# uart-keyboard.net
KiCad netlist of a schematic drawn in Altium Designer
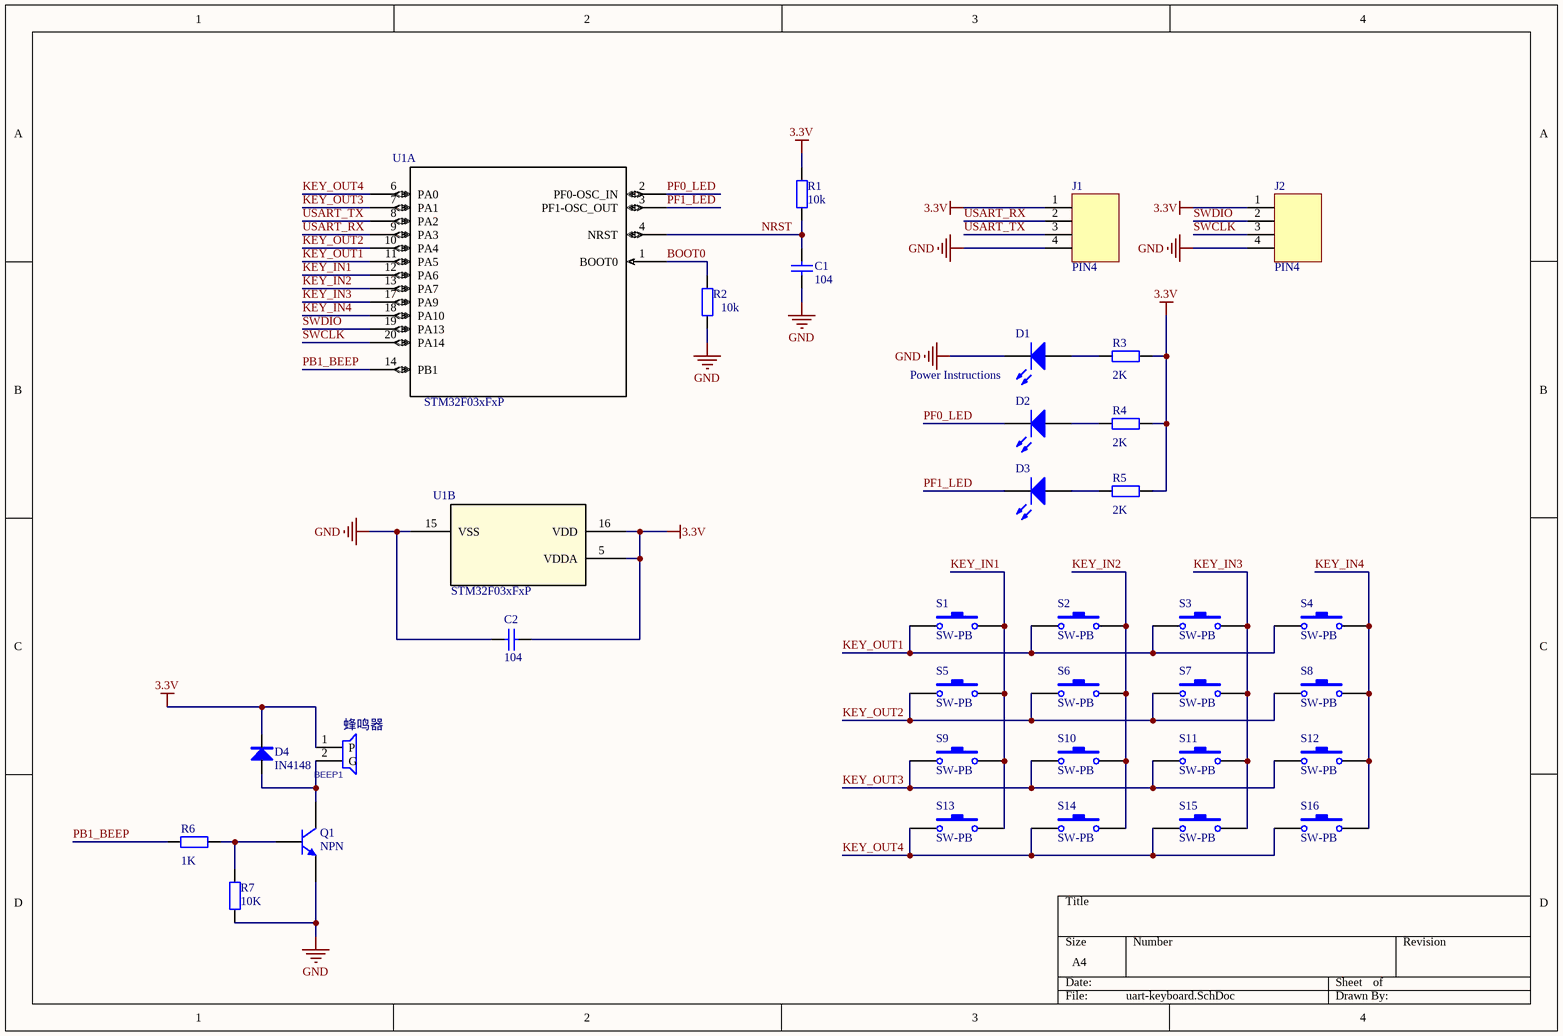
[diagram p0: uart-keyboard.SchDoc]

(export (version "E")
  (design (tool "Eeschema 10.0.6"))
  (components
    (comp (ref "BEEP1")
      (value "BEEP-9.5X5.5")
      (footprint "蜂鸣器")
      (libsource (lib "F429_F746_MB_SCH") (part "BEEP-9.5X5.5"))
    )
    (comp (ref "C1")
      (value "104")
      (footprint "0805C")
      (description "Capacitor")
      (fields (field (name "PUBLISHER") "Altium Limited"))
      (libsource (lib "Miscellaneous Devices") (part "Cap"))
    )
    (comp (ref "C2")
      (value "104")
      (footprint "0805C")
      (description "Capacitor")
      (fields (field (name "PUBLISHER") "Altium Limited"))
      (libsource (lib "Miscellaneous Devices") (part "Cap"))
    )
    (comp (ref "D1")
      (value "Power Instructions")
      (footprint "LED0805")
      (description "Typical RED, GREEN, YELLOW, AMBER GaAs LED")
      (fields (field (name "PUBLISHER") "Altium Limited"))
      (libsource (lib "Miscellaneous Devices") (part "LED2"))
    )
    (comp (ref "D2")
      (value "~")
      (footprint "LED0805")
      (description "Typical RED, GREEN, YELLOW, AMBER GaAs LED")
      (fields (field (name "PUBLISHER") "Altium Limited"))
      (libsource (lib "Miscellaneous Devices") (part "LED2"))
    )
    (comp (ref "D3")
      (value "~")
      (footprint "LED0805")
      (description "Typical RED, GREEN, YELLOW, AMBER GaAs LED")
      (fields (field (name "PUBLISHER") "Altium Limited"))
      (libsource (lib "Miscellaneous Devices") (part "LED2"))
    )
    (comp (ref "D4")
      (value "IN4148")
      (footprint "D4148")
      (libsource (lib "My Library OF Sch") (part "IN4148"))
    )
    (comp (ref "J1")
      (value "PIN4")
      (footprint "排针1*4-2.54-直")
      (libsource (lib "libpowersupply") (part "PIN4"))
    )
    (comp (ref "J2")
      (value "PIN4")
      (footprint "排针1*4-2.54-直")
      (libsource (lib "libpowersupply") (part "PIN4"))
    )
    (comp (ref "Q1")
      (value "NPN")
      (footprint "SOT-23-3")
      (description "NPN Bipolar Transistor")
      (fields (field (name "PUBLISHER") "Altium Limited"))
      (libsource (lib "Miscellaneous Devices") (part "NPN"))
    )
    (comp (ref "R1")
      (value "10k")
      (footprint "0805R")
      (description "Resistor")
      (fields (field (name "PUBLISHER") "Altium Limited"))
      (libsource (lib "") (part "Res2_1"))
    )
    (comp (ref "R2")
      (value "10k")
      (footprint "0805R")
      (description "Resistor")
      (fields (field (name "PUBLISHER") "Altium Limited"))
      (libsource (lib "") (part "Res2_2"))
    )
    (comp (ref "R3")
      (value "2K")
      (footprint "0805R")
      (description "Resistor")
      (fields (field (name "PUBLISHER") "Altium Limited"))
      (libsource (lib "Miscellaneous Devices") (part "Res2"))
    )
    (comp (ref "R4")
      (value "2K")
      (footprint "0805R")
      (description "Resistor")
      (fields (field (name "PUBLISHER") "Altium Limited"))
      (libsource (lib "Miscellaneous Devices") (part "Res2"))
    )
    (comp (ref "R5")
      (value "2K")
      (footprint "0805R")
      (description "Resistor")
      (fields (field (name "PUBLISHER") "Altium Limited"))
      (libsource (lib "Miscellaneous Devices") (part "Res2"))
    )
    (comp (ref "R6")
      (value "1K")
      (footprint "0805R")
      (description "Resistor")
      (fields (field (name "PUBLISHER") "Altium Limited"))
      (libsource (lib "Miscellaneous Devices") (part "Res2"))
    )
    (comp (ref "R7")
      (value "10K")
      (footprint "0805R")
      (description "Resistor")
      (fields (field (name "PUBLISHER") "Altium Limited"))
      (libsource (lib "") (part "Res2_3"))
    )
    (comp (ref "S1")
      (value "SW-PB")
      (footprint "轻触开关-6*6*5")
      (description "Switch")
      (fields (field (name "PUBLISHER") "Altium Limited"))
      (libsource (lib "Miscellaneous Devices") (part "SW-PB"))
    )
    (comp (ref "S2")
      (value "SW-PB")
      (footprint "轻触开关-6*6*5")
      (description "Switch")
      (fields (field (name "PUBLISHER") "Altium Limited"))
      (libsource (lib "Miscellaneous Devices") (part "SW-PB"))
    )
    (comp (ref "S3")
      (value "SW-PB")
      (footprint "轻触开关-6*6*5")
      (description "Switch")
      (fields (field (name "PUBLISHER") "Altium Limited"))
      (libsource (lib "Miscellaneous Devices") (part "SW-PB"))
    )
    (comp (ref "S4")
      (value "SW-PB")
      (footprint "轻触开关-6*6*5")
      (description "Switch")
      (fields (field (name "PUBLISHER") "Altium Limited"))
      (libsource (lib "Miscellaneous Devices") (part "SW-PB"))
    )
    (comp (ref "S5")
      (value "SW-PB")
      (footprint "轻触开关-6*6*5")
      (description "Switch")
      (fields (field (name "PUBLISHER") "Altium Limited"))
      (libsource (lib "Miscellaneous Devices") (part "SW-PB"))
    )
    (comp (ref "S6")
      (value "SW-PB")
      (footprint "轻触开关-6*6*5")
      (description "Switch")
      (fields (field (name "PUBLISHER") "Altium Limited"))
      (libsource (lib "Miscellaneous Devices") (part "SW-PB"))
    )
    (comp (ref "S7")
      (value "SW-PB")
      (footprint "轻触开关-6*6*5")
      (description "Switch")
      (fields (field (name "PUBLISHER") "Altium Limited"))
      (libsource (lib "Miscellaneous Devices") (part "SW-PB"))
    )
    (comp (ref "S8")
      (value "SW-PB")
      (footprint "轻触开关-6*6*5")
      (description "Switch")
      (fields (field (name "PUBLISHER") "Altium Limited"))
      (libsource (lib "Miscellaneous Devices") (part "SW-PB"))
    )
    (comp (ref "S9")
      (value "SW-PB")
      (footprint "轻触开关-6*6*5")
      (description "Switch")
      (fields (field (name "PUBLISHER") "Altium Limited"))
      (libsource (lib "Miscellaneous Devices") (part "SW-PB"))
    )
    (comp (ref "S10")
      (value "SW-PB")
      (footprint "轻触开关-6*6*5")
      (description "Switch")
      (fields (field (name "PUBLISHER") "Altium Limited"))
      (libsource (lib "Miscellaneous Devices") (part "SW-PB"))
    )
    (comp (ref "S11")
      (value "SW-PB")
      (footprint "轻触开关-6*6*5")
      (description "Switch")
      (fields (field (name "PUBLISHER") "Altium Limited"))
      (libsource (lib "Miscellaneous Devices") (part "SW-PB"))
    )
    (comp (ref "S12")
      (value "SW-PB")
      (footprint "轻触开关-6*6*5")
      (description "Switch")
      (fields (field (name "PUBLISHER") "Altium Limited"))
      (libsource (lib "Miscellaneous Devices") (part "SW-PB"))
    )
    (comp (ref "S13")
      (value "SW-PB")
      (footprint "轻触开关-6*6*5")
      (description "Switch")
      (fields (field (name "PUBLISHER") "Altium Limited"))
      (libsource (lib "Miscellaneous Devices") (part "SW-PB"))
    )
    (comp (ref "S14")
      (value "SW-PB")
      (footprint "轻触开关-6*6*5")
      (description "Switch")
      (fields (field (name "PUBLISHER") "Altium Limited"))
      (libsource (lib "Miscellaneous Devices") (part "SW-PB"))
    )
    (comp (ref "S15")
      (value "SW-PB")
      (footprint "轻触开关-6*6*5")
      (description "Switch")
      (fields (field (name "PUBLISHER") "Altium Limited"))
      (libsource (lib "Miscellaneous Devices") (part "SW-PB"))
    )
    (comp (ref "S16")
      (value "SW-PB")
      (footprint "轻触开关-6*6*5")
      (description "Switch")
      (fields (field (name "PUBLISHER") "Altium Limited"))
      (libsource (lib "Miscellaneous Devices") (part "SW-PB"))
    )
    (comp (ref "U1")
      (value "STM32F03xFxP")
      (footprint "TSSOP20")
      (description "Imported")
      (fields
        (field (name "MANUFACTURER_PART_NUMBER") "stm32f03xfxp")
        (field (name "COPYRIGHT") "Copyright (C) 2016 Accelerated Designs. All rights reserved")
      )
      (libsource (lib "stm32f030f4p6") (part "STM32F03xFxP"))
    )
  )
  (nets
    (net (code "1") (name "/BOOT0") (class "Default")
      (node (ref "R2") (pin "1") (pinfunction "1_1") (pintype "passive"))
      (node (ref "U1") (pin "1") (pinfunction "BOOT0_1") (pintype "input"))
    )
    (net (code "2") (name "/KEY_IN1") (class "Default")
      (node (ref "S1") (pin "2") (pinfunction "2_2") (pintype "passive"))
      (node (ref "S13") (pin "2") (pinfunction "2_2") (pintype "passive"))
      (node (ref "S5") (pin "2") (pinfunction "2_2") (pintype "passive"))
      (node (ref "S9") (pin "2") (pinfunction "2_2") (pintype "passive"))
      (node (ref "U1") (pin "12") (pinfunction "PA6_12") (pintype "bidirectional"))
    )
    (net (code "3") (name "/KEY_IN2") (class "Default")
      (node (ref "S10") (pin "2") (pinfunction "2_2") (pintype "passive"))
      (node (ref "S14") (pin "2") (pinfunction "2_2") (pintype "passive"))
      (node (ref "S2") (pin "2") (pinfunction "2_2") (pintype "passive"))
      (node (ref "S6") (pin "2") (pinfunction "2_2") (pintype "passive"))
      (node (ref "U1") (pin "13") (pinfunction "PA7_13") (pintype "bidirectional"))
    )
    (net (code "4") (name "/KEY_IN3") (class "Default")
      (node (ref "S11") (pin "2") (pinfunction "2_2") (pintype "passive"))
      (node (ref "S15") (pin "2") (pinfunction "2_2") (pintype "passive"))
      (node (ref "S3") (pin "2") (pinfunction "2_2") (pintype "passive"))
      (node (ref "S7") (pin "2") (pinfunction "2_2") (pintype "passive"))
      (node (ref "U1") (pin "17") (pinfunction "PA9_17") (pintype "bidirectional"))
    )
    (net (code "5") (name "/KEY_IN4") (class "Default")
      (node (ref "S12") (pin "2") (pinfunction "2_2") (pintype "passive"))
      (node (ref "S16") (pin "2") (pinfunction "2_2") (pintype "passive"))
      (node (ref "S4") (pin "2") (pinfunction "2_2") (pintype "passive"))
      (node (ref "S8") (pin "2") (pinfunction "2_2") (pintype "passive"))
      (node (ref "U1") (pin "18") (pinfunction "PA10_18") (pintype "bidirectional"))
    )
    (net (code "6") (name "/KEY_OUT1") (class "Default")
      (node (ref "S1") (pin "1") (pinfunction "1_1") (pintype "passive"))
      (node (ref "S2") (pin "1") (pinfunction "1_1") (pintype "passive"))
      (node (ref "S3") (pin "1") (pinfunction "1_1") (pintype "passive"))
      (node (ref "S4") (pin "1") (pinfunction "1_1") (pintype "passive"))
      (node (ref "U1") (pin "11") (pinfunction "PA5_11") (pintype "bidirectional"))
    )
    (net (code "7") (name "/KEY_OUT2") (class "Default")
      (node (ref "S5") (pin "1") (pinfunction "1_1") (pintype "passive"))
      (node (ref "S6") (pin "1") (pinfunction "1_1") (pintype "passive"))
      (node (ref "S7") (pin "1") (pinfunction "1_1") (pintype "passive"))
      (node (ref "S8") (pin "1") (pinfunction "1_1") (pintype "passive"))
      (node (ref "U1") (pin "10") (pinfunction "PA4_10") (pintype "bidirectional"))
    )
    (net (code "8") (name "/KEY_OUT3") (class "Default")
      (node (ref "S10") (pin "1") (pinfunction "1_1") (pintype "passive"))
      (node (ref "S11") (pin "1") (pinfunction "1_1") (pintype "passive"))
      (node (ref "S12") (pin "1") (pinfunction "1_1") (pintype "passive"))
      (node (ref "S9") (pin "1") (pinfunction "1_1") (pintype "passive"))
      (node (ref "U1") (pin "7") (pinfunction "PA1_7") (pintype "bidirectional"))
    )
    (net (code "9") (name "/KEY_OUT4") (class "Default")
      (node (ref "S13") (pin "1") (pinfunction "1_1") (pintype "passive"))
      (node (ref "S14") (pin "1") (pinfunction "1_1") (pintype "passive"))
      (node (ref "S15") (pin "1") (pinfunction "1_1") (pintype "passive"))
      (node (ref "S16") (pin "1") (pinfunction "1_1") (pintype "passive"))
      (node (ref "U1") (pin "6") (pinfunction "PA0_6") (pintype "bidirectional"))
    )
    (net (code "10") (name "/NRST") (class "Default")
      (node (ref "C1") (pin "2") (pinfunction "2_2") (pintype "passive"))
      (node (ref "R1") (pin "2") (pinfunction "2_2") (pintype "passive"))
      (node (ref "U1") (pin "4") (pinfunction "NRST_4") (pintype "bidirectional"))
    )
    (net (code "11") (name "/PB1_BEEP") (class "Default")
      (node (ref "R6") (pin "1") (pinfunction "1_1") (pintype "passive"))
      (node (ref "U1") (pin "14") (pinfunction "PB1_14") (pintype "bidirectional"))
    )
    (net (code "12") (name "/PF0_LED") (class "Default")
      (node (ref "D2") (pin "2") (pinfunction "K_2") (pintype "passive"))
      (node (ref "U1") (pin "2") (pinfunction "PF0-OSC_IN_2") (pintype "bidirectional"))
    )
    (net (code "13") (name "/PF1_LED") (class "Default")
      (node (ref "D3") (pin "2") (pinfunction "K_2") (pintype "passive"))
      (node (ref "U1") (pin "3") (pinfunction "PF1-OSC_OUT_3") (pintype "bidirectional"))
    )
    (net (code "14") (name "/SWCLK") (class "Default")
      (node (ref "J2") (pin "3") (pinfunction "3_3") (pintype "passive"))
      (node (ref "U1") (pin "20") (pinfunction "PA14_20") (pintype "bidirectional"))
    )
    (net (code "15") (name "/SWDIO") (class "Default")
      (node (ref "J2") (pin "2") (pinfunction "2_2") (pintype "passive"))
      (node (ref "U1") (pin "19") (pinfunction "PA13_19") (pintype "bidirectional"))
    )
    (net (code "16") (name "/USART_RX") (class "Default")
      (node (ref "J1") (pin "2") (pinfunction "2_2") (pintype "passive"))
      (node (ref "U1") (pin "9") (pinfunction "PA3_9") (pintype "bidirectional"))
    )
    (net (code "17") (name "/USART_TX") (class "Default")
      (node (ref "J1") (pin "3") (pinfunction "3_3") (pintype "passive"))
      (node (ref "U1") (pin "8") (pinfunction "PA2_8") (pintype "bidirectional"))
    )
    (net (code "18") (name "3.3V") (class "Default")
      (node (ref "BEEP1") (pin "1") (pinfunction "P_1") (pintype "passive"))
      (node (ref "C2") (pin "1") (pinfunction "1_1") (pintype "passive"))
      (node (ref "D4") (pin "2") (pinfunction "K_2") (pintype "passive"))
      (node (ref "J1") (pin "1") (pinfunction "1_1") (pintype "passive"))
      (node (ref "J2") (pin "1") (pinfunction "1_1") (pintype "passive"))
      (node (ref "R1") (pin "1") (pinfunction "1_1") (pintype "passive"))
      (node (ref "R3") (pin "2") (pinfunction "2_2") (pintype "passive"))
      (node (ref "R4") (pin "2") (pinfunction "2_2") (pintype "passive"))
      (node (ref "R5") (pin "2") (pinfunction "2_2") (pintype "passive"))
      (node (ref "U1") (pin "16") (pinfunction "VDD_16") (pintype "power_in"))
      (node (ref "U1") (pin "5") (pinfunction "VDDA_5") (pintype "power_in"))
    )
    (net (code "19") (name "GND") (class "Default")
      (node (ref "C1") (pin "1") (pinfunction "1_1") (pintype "passive"))
      (node (ref "C2") (pin "2") (pinfunction "2_2") (pintype "passive"))
      (node (ref "D1") (pin "2") (pinfunction "K_2") (pintype "passive"))
      (node (ref "J1") (pin "4") (pinfunction "4_4") (pintype "passive"))
      (node (ref "J2") (pin "4") (pinfunction "4_4") (pintype "passive"))
      (node (ref "Q1") (pin "E") (pinfunction "E_E") (pintype "passive"))
      (node (ref "R2") (pin "2") (pinfunction "2_2") (pintype "passive"))
      (node (ref "R7") (pin "1") (pinfunction "1_1") (pintype "passive"))
      (node (ref "U1") (pin "15") (pinfunction "VSS_15") (pintype "power_in"))
    )
    (net (code "20") (name "Net-(BEEP1-G)") (class "Default")
      (node (ref "BEEP1") (pin "2") (pinfunction "G_2") (pintype "passive"))
      (node (ref "D4") (pin "1") (pinfunction "A_1") (pintype "passive"))
      (node (ref "Q1") (pin "C") (pinfunction "C_C") (pintype "passive"))
    )
    (net (code "21") (name "Net-(D1-A)") (class "Default")
      (node (ref "D1") (pin "1") (pinfunction "A_1") (pintype "passive"))
      (node (ref "R3") (pin "1") (pinfunction "1_1") (pintype "passive"))
    )
    (net (code "22") (name "Net-(D2-A)") (class "Default")
      (node (ref "D2") (pin "1") (pinfunction "A_1") (pintype "passive"))
      (node (ref "R4") (pin "1") (pinfunction "1_1") (pintype "passive"))
    )
    (net (code "23") (name "Net-(D3-A)") (class "Default")
      (node (ref "D3") (pin "1") (pinfunction "A_1") (pintype "passive"))
      (node (ref "R5") (pin "1") (pinfunction "1_1") (pintype "passive"))
    )
    (net (code "24") (name "Net-(Q1-PadB)") (class "Default")
      (node (ref "Q1") (pin "B") (pinfunction "B_B") (pintype "passive"))
      (node (ref "R6") (pin "2") (pinfunction "2_2") (pintype "passive"))
      (node (ref "R7") (pin "2") (pinfunction "2_2") (pintype "passive"))
    )
  )
)
